# MMI.net
KiCad netlist of a schematic drawn in Altium Designer
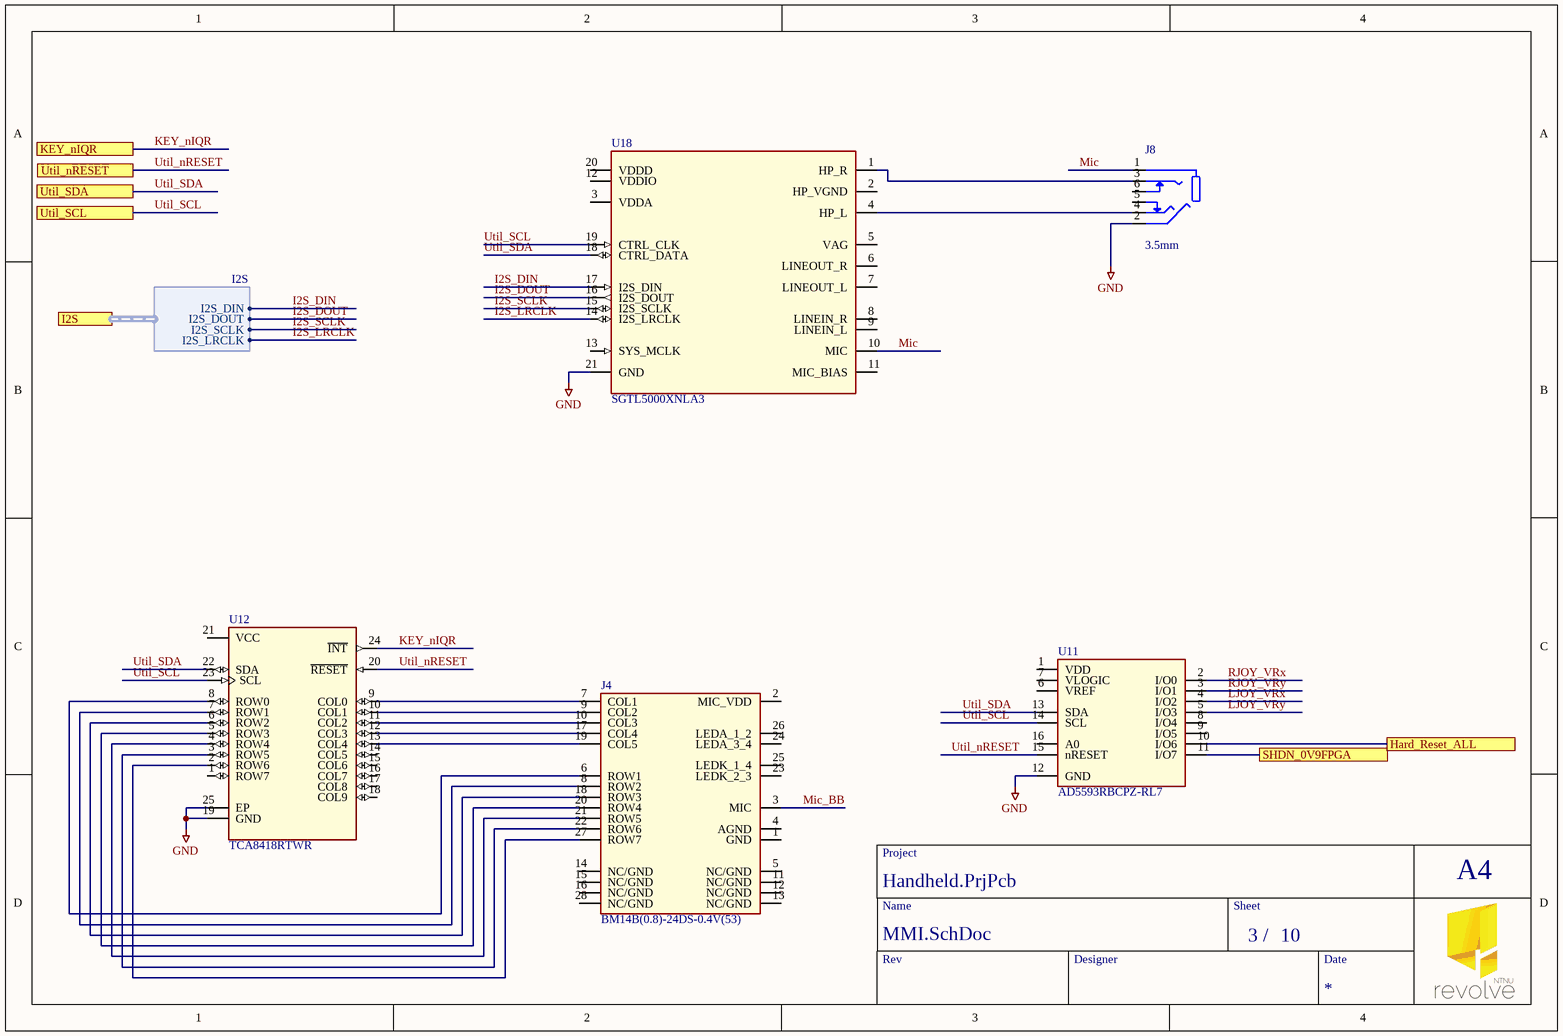
[diagram p0: MMI.SchDoc]

(export (version "E")
  (design (tool "Eeschema 10.0.6"))
  (components
    (comp (ref "J4")
      (value "BM14B(0.8)-24DS-0.4V(53)")
      (footprint "CONN24_BM14B_HIR")
      (description "BB Q10 keyboard connector")
      (fields (field (name "COPYRIGHT") "Copyright (C) 2025 Ultra Librarian. All rights reserved."))
      (libsource (lib "Handheld") (part "BM14B0.8-24DS-0.4V53"))
    )
    (comp (ref "J8")
      (value "3.5mm")
      (footprint "TENSILITY_54-00176")
      (description "Connector, 4C audio jack, 3.5xL14 mm, thru hole, gold plated")
      (fields (field (name "MF") "Tensility International Corp") (field (name "MP") "54-00176"))
      (libsource (lib "Handheld") (part "54-00176"))
    )
    (comp (ref "U11")
      (value "AD5593RBCPZ-RL7")
      (footprint "CP_16_32_ADI-M")
      (description "8-Channel, 12-Bit, Configurable ADC/DAC with On-Chip Reference, I2C Interface")
      (fields (field (name "COPYRIGHT") "Copyright (C) 2025 Ultra Librarian. All rights reserved."))
      (libsource (lib "Handheld") (part "AD5593RBCPZ-RL7"))
    )
    (comp (ref "U12")
      (value "TCA8418RTWR")
      (footprint "QFN50P400X400X80-25N")
      (description "I2C Controlled Keypad Scan IC With Integrated ESD Protection 24-WQFN -40 to 85")
      (fields (field (name "MF") "Texas Instruments") (field (name "DIGI-KEY_PART_NUMBER") "296-25223-1-ND"))
      (libsource (lib "Handheld") (part "TCA8418RTWR"))
    )
    (comp (ref "U18")
      (value "SGTL5000XNLA3")
      (footprint "HUQFN20_SOT1628-1_NXP-M")
      (description "IC AUDIO CODEC STEREO 20-QFN")
      (fields (field (name "COPYRIGHT") "Copyright (C) 2025 Ultra Librarian. All rights reserved."))
      (libsource (lib "Handheld") (part "SGTL5000XNLA3"))
    )
  )
  (nets
    (net (code "2") (name "/Hard_Reset_ALL") (class "Default")
      (node (ref "U11") (pin "10") (pinfunction "I/O6_10") (pintype "passive"))
    )
    (net (code "3") (name "/I2S_DIN") (class "Default")
      (node (ref "U18") (pin "17") (pinfunction "I2S_DIN_17") (pintype "input"))
    )
    (net (code "4") (name "/I2S_DOUT") (class "Default")
      (node (ref "U18") (pin "16") (pinfunction "I2S_DOUT_16") (pintype "output"))
    )
    (net (code "5") (name "/I2S_LRCLK") (class "Default")
      (node (ref "U18") (pin "14") (pinfunction "I2S_LRCLK_14") (pintype "bidirectional"))
    )
    (net (code "6") (name "/I2S_SCLK") (class "Default")
      (node (ref "U18") (pin "15") (pinfunction "I2S_SCLK_15") (pintype "bidirectional"))
    )
    (net (code "7") (name "/KEY_nIQR") (class "Default")
      (node (ref "U12") (pin "24") (pinfunction "~{INT}_24") (pintype "output"))
    )
    (net (code "8") (name "/LJOY_VRx") (class "Default")
      (node (ref "U11") (pin "4") (pinfunction "I/O2_4") (pintype "passive"))
    )
    (net (code "9") (name "/LJOY_VRy") (class "Default")
      (node (ref "U11") (pin "5") (pinfunction "I/O3_5") (pintype "passive"))
    )
    (net (code "10") (name "/Mic") (class "Default")
      (node (ref "J8") (pin "1") (pinfunction "1_1") (pintype "passive"))
      (node (ref "U18") (pin "10") (pinfunction "MIC_10") (pintype "passive"))
    )
    (net (code "11") (name "/Mic_BB") (class "Default")
      (node (ref "J4") (pin "3") (pinfunction "MIC_3") (pintype "passive"))
    )
    (net (code "12") (name "/RJOY_VRx") (class "Default")
      (node (ref "U11") (pin "2") (pinfunction "I/O0_2") (pintype "passive"))
    )
    (net (code "13") (name "/RJOY_VRy") (class "Default")
      (node (ref "U11") (pin "3") (pinfunction "I/O1_3") (pintype "passive"))
    )
    (net (code "14") (name "/SHDN_0V9FPGA") (class "Default")
      (node (ref "U11") (pin "11") (pinfunction "I/O7_11") (pintype "passive"))
    )
    (net (code "15") (name "/Util_SCL") (class "Default")
      (node (ref "U11") (pin "14") (pinfunction "SCL_14") (pintype "passive"))
      (node (ref "U12") (pin "23") (pinfunction "SCL_23") (pintype "input"))
      (node (ref "U18") (pin "19") (pinfunction "CTRL_CLK_19") (pintype "input"))
    )
    (net (code "16") (name "/Util_SDA") (class "Default")
      (node (ref "U11") (pin "13") (pinfunction "SDA_13") (pintype "passive"))
      (node (ref "U12") (pin "22") (pinfunction "SDA_22") (pintype "bidirectional"))
      (node (ref "U18") (pin "18") (pinfunction "CTRL_DATA_18") (pintype "bidirectional"))
    )
    (net (code "17") (name "/Util_nRESET") (class "Default")
      (node (ref "U11") (pin "15") (pinfunction "nRESET_15") (pintype "passive"))
      (node (ref "U12") (pin "20") (pinfunction "~{RESET}_20") (pintype "input"))
    )
    (net (code "19") (name "GND") (class "Default")
      (node (ref "J8") (pin "2") (pinfunction "2_2") (pintype "passive"))
      (node (ref "U11") (pin "12") (pinfunction "GND_12") (pintype "passive"))
      (node (ref "U12") (pin "19") (pinfunction "GND_19") (pintype "power_in"))
      (node (ref "U12") (pin "25") (pinfunction "EP_25") (pintype "passive"))
      (node (ref "U18") (pin "21") (pinfunction "GND_21") (pintype "power_in"))
    )
    (net (code "20") (name "Net-(J4-COL1)") (class "Default")
      (node (ref "J4") (pin "7") (pinfunction "COL1_7") (pintype "passive"))
      (node (ref "U12") (pin "9") (pinfunction "COL0_9") (pintype "bidirectional"))
    )
    (net (code "21") (name "Net-(J4-COL2)") (class "Default")
      (node (ref "J4") (pin "9") (pinfunction "COL2_9") (pintype "passive"))
      (node (ref "U12") (pin "10") (pinfunction "COL1_10") (pintype "bidirectional"))
    )
    (net (code "22") (name "Net-(J4-COL3)") (class "Default")
      (node (ref "J4") (pin "10") (pinfunction "COL3_10") (pintype "passive"))
      (node (ref "U12") (pin "11") (pinfunction "COL2_11") (pintype "bidirectional"))
    )
    (net (code "23") (name "Net-(J4-COL4)") (class "Default")
      (node (ref "J4") (pin "17") (pinfunction "COL4_17") (pintype "passive"))
      (node (ref "U12") (pin "12") (pinfunction "COL3_12") (pintype "bidirectional"))
    )
    (net (code "24") (name "Net-(J4-COL5)") (class "Default")
      (node (ref "J4") (pin "19") (pinfunction "COL5_19") (pintype "passive"))
      (node (ref "U12") (pin "13") (pinfunction "COL4_13") (pintype "bidirectional"))
    )
    (net (code "25") (name "Net-(J4-ROW1)") (class "Default")
      (node (ref "J4") (pin "6") (pinfunction "ROW1_6") (pintype "passive"))
      (node (ref "U12") (pin "8") (pinfunction "ROW0_8") (pintype "bidirectional"))
    )
    (net (code "26") (name "Net-(J4-ROW2)") (class "Default")
      (node (ref "J4") (pin "8") (pinfunction "ROW2_8") (pintype "passive"))
      (node (ref "U12") (pin "7") (pinfunction "ROW1_7") (pintype "bidirectional"))
    )
    (net (code "27") (name "Net-(J4-ROW3)") (class "Default")
      (node (ref "J4") (pin "18") (pinfunction "ROW3_18") (pintype "passive"))
      (node (ref "U12") (pin "6") (pinfunction "ROW2_6") (pintype "bidirectional"))
    )
    (net (code "28") (name "Net-(J4-ROW4)") (class "Default")
      (node (ref "J4") (pin "20") (pinfunction "ROW4_20") (pintype "passive"))
      (node (ref "U12") (pin "5") (pinfunction "ROW3_5") (pintype "bidirectional"))
    )
    (net (code "29") (name "Net-(J4-ROW5)") (class "Default")
      (node (ref "J4") (pin "21") (pinfunction "ROW5_21") (pintype "passive"))
      (node (ref "U12") (pin "4") (pinfunction "ROW4_4") (pintype "bidirectional"))
    )
    (net (code "30") (name "Net-(J4-ROW6)") (class "Default")
      (node (ref "J4") (pin "22") (pinfunction "ROW6_22") (pintype "passive"))
      (node (ref "U12") (pin "3") (pinfunction "ROW5_3") (pintype "bidirectional"))
    )
    (net (code "31") (name "Net-(J4-ROW7)") (class "Default")
      (node (ref "J4") (pin "27") (pinfunction "ROW7_27") (pintype "passive"))
      (node (ref "U12") (pin "2") (pinfunction "ROW6_2") (pintype "bidirectional"))
    )
    (net (code "32") (name "Net-(U18-HP_L)") (class "Default")
      (node (ref "J8") (pin "4") (pinfunction "4_4") (pintype "passive"))
      (node (ref "U18") (pin "4") (pinfunction "HP_L_4") (pintype "passive"))
    )
    (net (code "33") (name "Net-(U18-HP_R)") (class "Default")
      (node (ref "J8") (pin "3") (pinfunction "3_3") (pintype "passive"))
      (node (ref "U18") (pin "1") (pinfunction "HP_R_1") (pintype "passive"))
    )
    (net (code "34") (name "unconnected-(J4-AGND-Pad4)") (class "Default")
      (node (ref "J4") (pin "4") (pinfunction "AGND_4") (pintype "passive"))
    )
    (net (code "35") (name "unconnected-(J4-GND-Pad1)") (class "Default")
      (node (ref "J4") (pin "1") (pinfunction "GND_1") (pintype "passive"))
    )
    (net (code "36") (name "unconnected-(J4-LEDA_1_2-Pad26)") (class "Default")
      (node (ref "J4") (pin "26") (pinfunction "LEDA_1_2_26") (pintype "passive"))
    )
    (net (code "37") (name "unconnected-(J4-LEDA_3_4-Pad24)") (class "Default")
      (node (ref "J4") (pin "24") (pinfunction "LEDA_3_4_24") (pintype "passive"))
    )
    (net (code "38") (name "unconnected-(J4-LEDK_1_4-Pad25)") (class "Default")
      (node (ref "J4") (pin "25") (pinfunction "LEDK_1_4_25") (pintype "passive"))
    )
    (net (code "39") (name "unconnected-(J4-LEDK_2_3-Pad23)") (class "Default")
      (node (ref "J4") (pin "23") (pinfunction "LEDK_2_3_23") (pintype "passive"))
    )
    (net (code "40") (name "unconnected-(J4-MIC_VDD-Pad2)") (class "Default")
      (node (ref "J4") (pin "2") (pinfunction "MIC_VDD_2") (pintype "passive"))
    )
    (net (code "41") (name "unconnected-(J4-NC{slash}GND-Pad5)") (class "Default")
      (node (ref "J4") (pin "5") (pinfunction "NC/GND_5") (pintype "passive"))
    )
    (net (code "42") (name "unconnected-(J4-NC{slash}GND-Pad11)") (class "Default")
      (node (ref "J4") (pin "11") (pinfunction "NC/GND_11") (pintype "passive"))
    )
    (net (code "43") (name "unconnected-(J4-NC{slash}GND-Pad12)") (class "Default")
      (node (ref "J4") (pin "12") (pinfunction "NC/GND_12") (pintype "passive"))
    )
    (net (code "44") (name "unconnected-(J4-NC{slash}GND-Pad13)") (class "Default")
      (node (ref "J4") (pin "13") (pinfunction "NC/GND_13") (pintype "passive"))
    )
    (net (code "45") (name "unconnected-(J4-NC{slash}GND-Pad14)") (class "Default")
      (node (ref "J4") (pin "14") (pinfunction "NC/GND_14") (pintype "passive"))
    )
    (net (code "46") (name "unconnected-(J4-NC{slash}GND-Pad15)") (class "Default")
      (node (ref "J4") (pin "15") (pinfunction "NC/GND_15") (pintype "passive"))
    )
    (net (code "47") (name "unconnected-(J4-NC{slash}GND-Pad16)") (class "Default")
      (node (ref "J4") (pin "16") (pinfunction "NC/GND_16") (pintype "passive"))
    )
    (net (code "48") (name "unconnected-(J4-NC{slash}GND-Pad28)") (class "Default")
      (node (ref "J4") (pin "28") (pinfunction "NC/GND_28") (pintype "passive"))
    )
    (net (code "49") (name "unconnected-(J8-Pad5)") (class "Default")
      (node (ref "J8") (pin "5") (pinfunction "5_5") (pintype "passive"))
    )
    (net (code "50") (name "unconnected-(J8-Pad6)") (class "Default")
      (node (ref "J8") (pin "6") (pinfunction "6_6") (pintype "passive"))
    )
    (net (code "51") (name "unconnected-(U11-A0-Pad16)") (class "Default")
      (node (ref "U11") (pin "16") (pinfunction "A0_16") (pintype "passive"))
    )
    (net (code "52") (name "unconnected-(U11-I{slash}O4-Pad8)") (class "Default")
      (node (ref "U11") (pin "8") (pinfunction "I/O4_8") (pintype "passive"))
    )
    (net (code "53") (name "unconnected-(U11-I{slash}O5-Pad9)") (class "Default")
      (node (ref "U11") (pin "9") (pinfunction "I/O5_9") (pintype "passive"))
    )
    (net (code "54") (name "unconnected-(U11-VDD-Pad1)") (class "Default")
      (node (ref "U11") (pin "1") (pinfunction "VDD_1") (pintype "passive"))
    )
    (net (code "55") (name "unconnected-(U11-VLOGIC-Pad7)") (class "Default")
      (node (ref "U11") (pin "7") (pinfunction "VLOGIC_7") (pintype "passive"))
    )
    (net (code "56") (name "unconnected-(U11-VREF-Pad6)") (class "Default")
      (node (ref "U11") (pin "6") (pinfunction "VREF_6") (pintype "passive"))
    )
    (net (code "57") (name "unconnected-(U12-COL5-Pad14)") (class "Default")
      (node (ref "U12") (pin "14") (pinfunction "COL5_14") (pintype "bidirectional"))
    )
    (net (code "58") (name "unconnected-(U12-COL6-Pad15)") (class "Default")
      (node (ref "U12") (pin "15") (pinfunction "COL6_15") (pintype "bidirectional"))
    )
    (net (code "59") (name "unconnected-(U12-COL7-Pad16)") (class "Default")
      (node (ref "U12") (pin "16") (pinfunction "COL7_16") (pintype "bidirectional"))
    )
    (net (code "60") (name "unconnected-(U12-COL8-Pad17)") (class "Default")
      (node (ref "U12") (pin "17") (pinfunction "COL8_17") (pintype "bidirectional"))
    )
    (net (code "61") (name "unconnected-(U12-COL9-Pad18)") (class "Default")
      (node (ref "U12") (pin "18") (pinfunction "COL9_18") (pintype "bidirectional"))
    )
    (net (code "62") (name "unconnected-(U12-ROW7-Pad1)") (class "Default")
      (node (ref "U12") (pin "1") (pinfunction "ROW7_1") (pintype "bidirectional"))
    )
    (net (code "63") (name "unconnected-(U12-VCC-Pad21)") (class "Default")
      (node (ref "U12") (pin "21") (pinfunction "VCC_21") (pintype "power_in"))
    )
    (net (code "64") (name "unconnected-(U18-HP_VGND-Pad2)") (class "Default")
      (node (ref "U18") (pin "2") (pinfunction "HP_VGND_2") (pintype "power_in"))
    )
    (net (code "65") (name "unconnected-(U18-LINEIN_L-Pad9)") (class "Default")
      (node (ref "U18") (pin "9") (pinfunction "LINEIN_L_9") (pintype "passive"))
    )
    (net (code "66") (name "unconnected-(U18-LINEIN_R-Pad8)") (class "Default")
      (node (ref "U18") (pin "8") (pinfunction "LINEIN_R_8") (pintype "passive"))
    )
    (net (code "67") (name "unconnected-(U18-LINEOUT_L-Pad7)") (class "Default")
      (node (ref "U18") (pin "7") (pinfunction "LINEOUT_L_7") (pintype "passive"))
    )
    (net (code "68") (name "unconnected-(U18-LINEOUT_R-Pad6)") (class "Default")
      (node (ref "U18") (pin "6") (pinfunction "LINEOUT_R_6") (pintype "passive"))
    )
    (net (code "69") (name "unconnected-(U18-MIC_BIAS-Pad11)") (class "Default")
      (node (ref "U18") (pin "11") (pinfunction "MIC_BIAS_11") (pintype "passive"))
    )
    (net (code "70") (name "unconnected-(U18-SYS_MCLK-Pad13)") (class "Default")
      (node (ref "U18") (pin "13") (pinfunction "SYS_MCLK_13") (pintype "input"))
    )
    (net (code "71") (name "unconnected-(U18-VAG-Pad5)") (class "Default")
      (node (ref "U18") (pin "5") (pinfunction "VAG_5") (pintype "passive"))
    )
    (net (code "72") (name "unconnected-(U18-VDDA-Pad3)") (class "Default")
      (node (ref "U18") (pin "3") (pinfunction "VDDA_3") (pintype "power_in"))
    )
    (net (code "73") (name "unconnected-(U18-VDDD-Pad20)") (class "Default")
      (node (ref "U18") (pin "20") (pinfunction "VDDD_20") (pintype "power_in"))
    )
    (net (code "74") (name "unconnected-(U18-VDDIO-Pad12)") (class "Default")
      (node (ref "U18") (pin "12") (pinfunction "VDDIO_12") (pintype "power_in"))
    )
  )
)
